# S03.net
KiCad netlist of a schematic drawn in Altium Designer
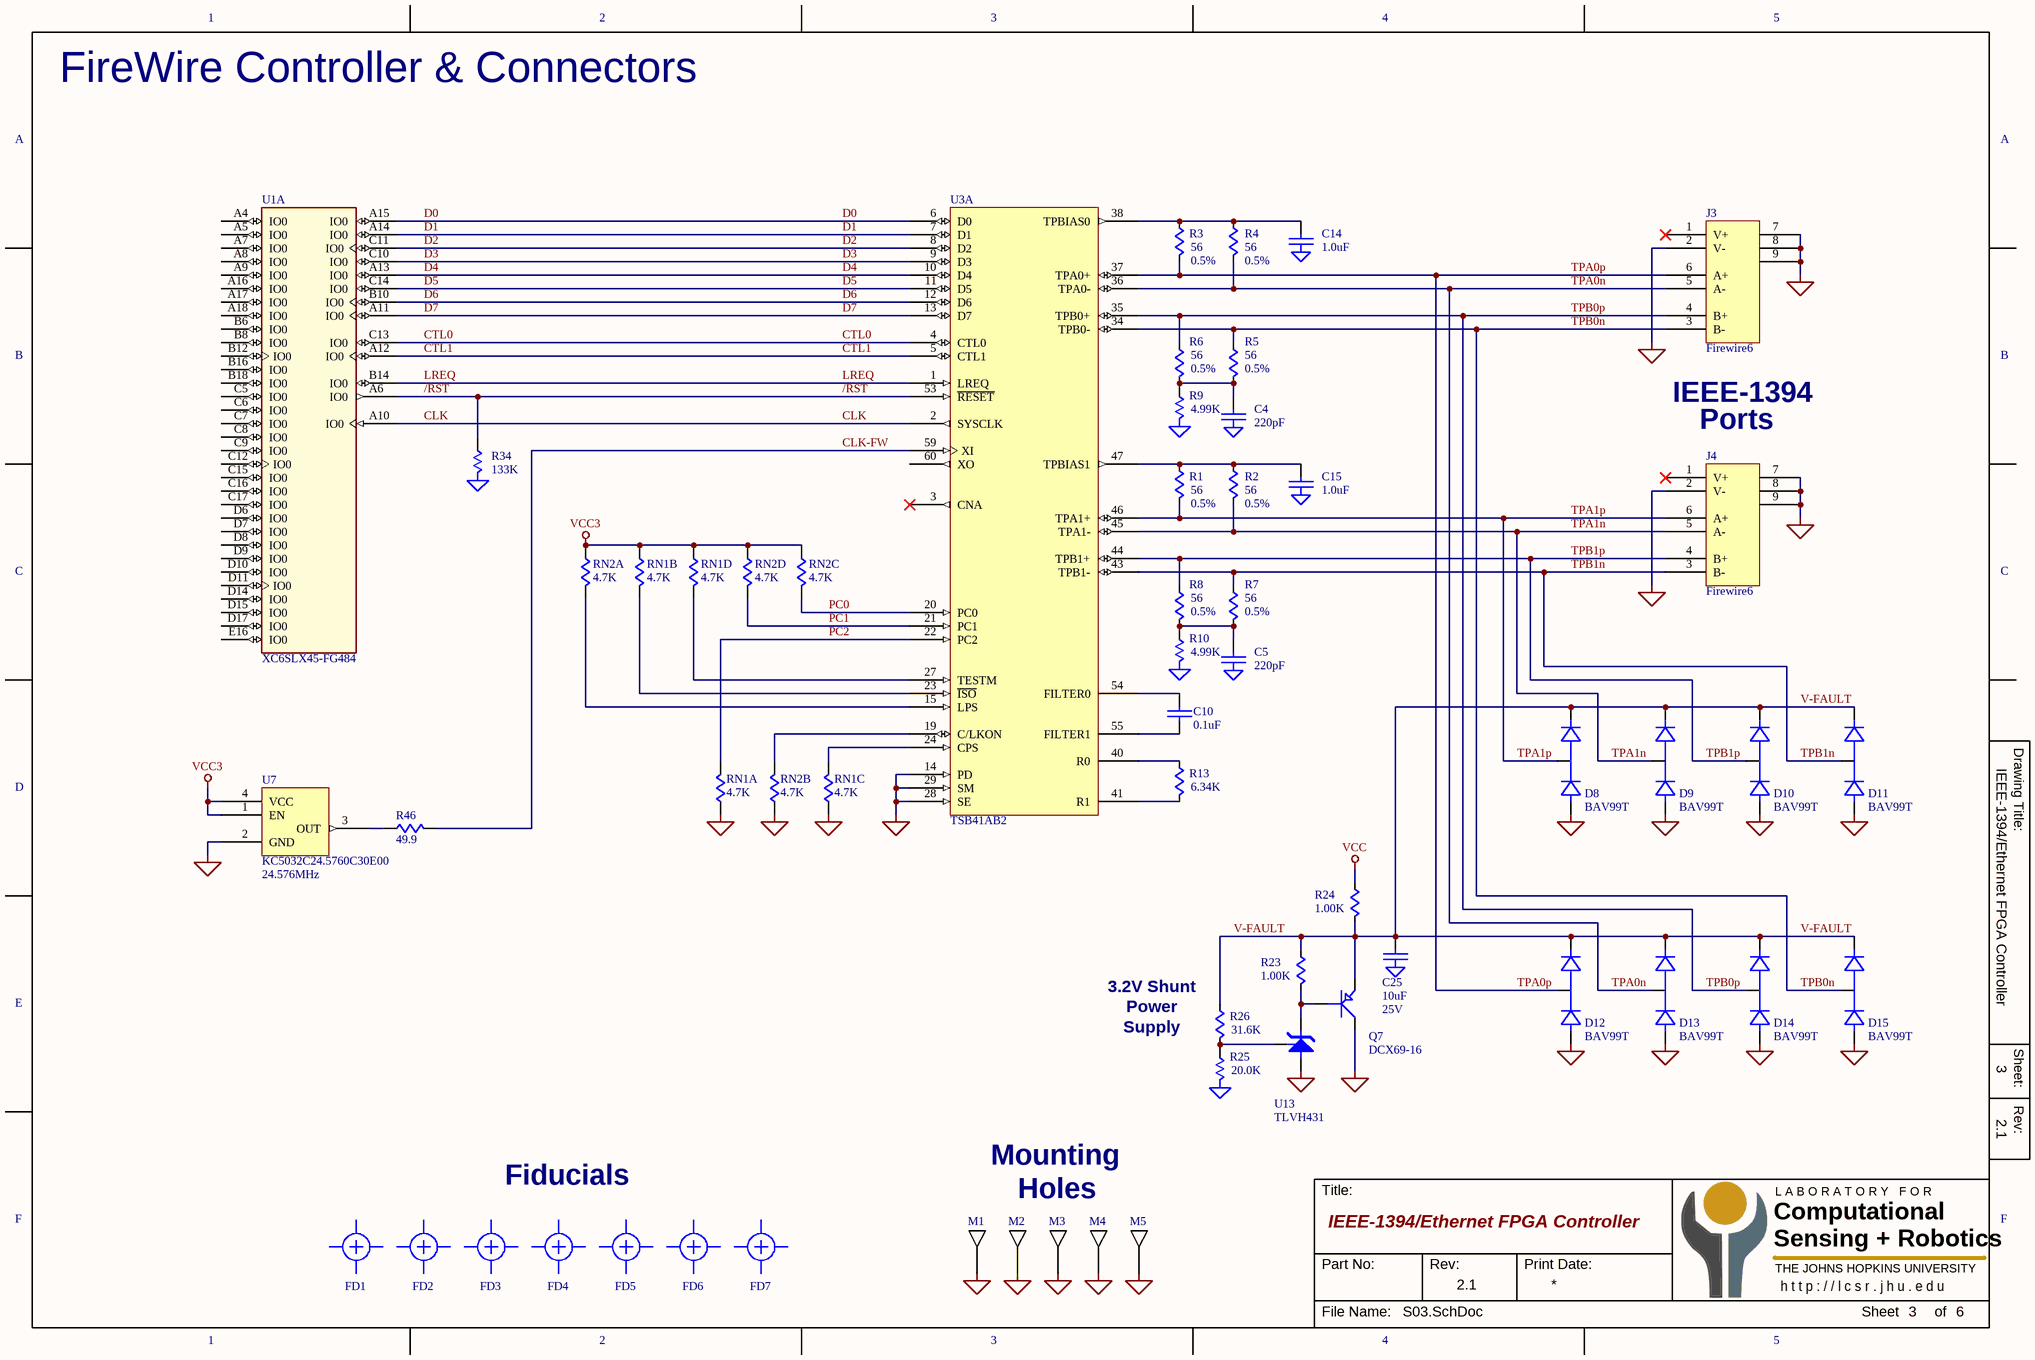
[diagram p0: S03.SchDoc]

(export (version "E")
  (design (tool "Eeschema 10.0.6"))
  (components
    (comp (ref "C4") (value "220pF") (footprint "C0603") (libsource (lib "LibJHU") (part "CAP-GND")))
    (comp (ref "C5") (value "220pF") (footprint "C0603") (libsource (lib "LibJHU") (part "CAP-GND")))
    (comp (ref "C10") (value "0.1uF") (footprint "C0603") (libsource (lib "LibJHU") (part "CAP")))
    (comp (ref "C14") (value "1.0uF") (footprint "C0603") (libsource (lib "LibJHU") (part "CAP-GND")))
    (comp (ref "C15") (value "1.0uF") (footprint "C0603") (libsource (lib "LibJHU") (part "CAP-GND")))
    (comp (ref "C25")
      (value "10uF")
      (footprint "C0805")
      (fields (field (name "ALTIUM_UNNAMED_1") "25V"))
      (libsource (lib "LibJHU") (part "CAP-GND"))
    )
    (comp (ref "D8") (value "BAV99T") (footprint "SOT-523") (libsource (lib "LibJHU") (part "DIODE-2/SER")))
    (comp (ref "D9") (value "BAV99T") (footprint "SOT-523") (libsource (lib "LibJHU") (part "DIODE-2/SER")))
    (comp (ref "D10") (value "BAV99T") (footprint "SOT-523") (libsource (lib "LibJHU") (part "DIODE-2/SER")))
    (comp (ref "D11") (value "BAV99T") (footprint "SOT-523") (libsource (lib "LibJHU") (part "DIODE-2/SER")))
    (comp (ref "D12") (value "BAV99T") (footprint "SOT-523") (libsource (lib "LibJHU") (part "DIODE-2/SER")))
    (comp (ref "D13") (value "BAV99T") (footprint "SOT-523") (libsource (lib "LibJHU") (part "DIODE-2/SER")))
    (comp (ref "D14") (value "BAV99T") (footprint "SOT-523") (libsource (lib "LibJHU") (part "DIODE-2/SER")))
    (comp (ref "D15") (value "BAV99T") (footprint "SOT-523") (libsource (lib "LibJHU") (part "DIODE-2/SER")))
    (comp (ref "FD1") (value "FD") (footprint "FD") (libsource (lib "LibJHU") (part "FD")))
    (comp (ref "FD2") (value "FD") (footprint "FD") (libsource (lib "LibJHU") (part "FD")))
    (comp (ref "FD3") (value "FD") (footprint "FD") (libsource (lib "LibJHU") (part "FD")))
    (comp (ref "FD4") (value "FD") (footprint "FD") (libsource (lib "LibJHU") (part "FD")))
    (comp (ref "FD5") (value "FD") (footprint "FD") (libsource (lib "LibJHU") (part "FD")))
    (comp (ref "FD6") (value "FD") (footprint "FD") (libsource (lib "LibJHU") (part "FD")))
    (comp (ref "FD7") (value "FD") (footprint "FD") (libsource (lib "LibJHU") (part "FD")))
    (comp (ref "J3")
      (value "Firewire6")
      (footprint "Firewire6-RA")
      (libsource (lib "LibJHU") (part "Firewire6"))
    )
    (comp (ref "J4")
      (value "Firewire6")
      (footprint "Firewire6-RA")
      (libsource (lib "LibJHU") (part "Firewire6"))
    )
    (comp (ref "M1")
      (value "MHOLE")
      (footprint "MHOLE4")
      (description "Mounting Hole")
      (libsource (lib "LibJHU") (part "MHOLE"))
    )
    (comp (ref "M2")
      (value "MHOLE")
      (footprint "MHOLE4")
      (description "Mounting Hole")
      (libsource (lib "LibJHU") (part "MHOLE"))
    )
    (comp (ref "M3")
      (value "MHOLE")
      (footprint "MHOLE4")
      (description "Mounting Hole")
      (libsource (lib "LibJHU") (part "MHOLE"))
    )
    (comp (ref "M4")
      (value "MHOLE")
      (footprint "MHOLE4")
      (description "Mounting Hole")
      (libsource (lib "LibJHU") (part "MHOLE"))
    )
    (comp (ref "M5")
      (value "MHOLE")
      (footprint "MHOLE4")
      (description "Mounting Hole")
      (libsource (lib "LibJHU") (part "MHOLE"))
    )
    (comp (ref "Q7") (value "DCX69-16") (footprint "SOT-89") (libsource (lib "LibJHU") (part "PNP-SM")))
    (comp (ref "R1")
      (value "56")
      (footprint "R0603")
      (fields (field (name "TOLL") "0.5%"))
      (libsource (lib "LibJHU") (part "R-MINI"))
    )
    (comp (ref "R2")
      (value "56")
      (footprint "R0603")
      (fields (field (name "TOLL") "0.5%"))
      (libsource (lib "LibJHU") (part "R-MINI"))
    )
    (comp (ref "R3")
      (value "56")
      (footprint "R0603")
      (fields (field (name "TOLL") "0.5%"))
      (libsource (lib "LibJHU") (part "R-MINI"))
    )
    (comp (ref "R4")
      (value "56")
      (footprint "R0603")
      (fields (field (name "TOLL") "0.5%"))
      (libsource (lib "LibJHU") (part "R-MINI"))
    )
    (comp (ref "R5")
      (value "56")
      (footprint "R0603")
      (fields (field (name "TOLL") "0.5%"))
      (libsource (lib "LibJHU") (part "R-MINI"))
    )
    (comp (ref "R6")
      (value "56")
      (footprint "R0603")
      (fields (field (name "TOLL") "0.5%"))
      (libsource (lib "LibJHU") (part "R-MINI"))
    )
    (comp (ref "R7")
      (value "56")
      (footprint "R0603")
      (fields (field (name "TOLL") "0.5%"))
      (libsource (lib "LibJHU") (part "R-MINI"))
    )
    (comp (ref "R8")
      (value "56")
      (footprint "R0603")
      (fields (field (name "TOLL") "0.5%"))
      (libsource (lib "LibJHU") (part "R-MINI"))
    )
    (comp (ref "R9") (value "4.99K") (footprint "R0603") (libsource (lib "") (part "R-GND_1")))
    (comp (ref "R10") (value "4.99K") (footprint "R0603") (libsource (lib "") (part "R-GND_1")))
    (comp (ref "R13") (value "6.34K") (footprint "R0603") (libsource (lib "LibJHU") (part "R-MINI")))
    (comp (ref "R23") (value "1.00K") (footprint "R0603") (libsource (lib "LibJHU") (part "R-MINI")))
    (comp (ref "R24") (value "1.00K") (footprint "R0603") (libsource (lib "LibJHU") (part "R-MINI")))
    (comp (ref "R25") (value "20.0K") (footprint "R0603") (libsource (lib "") (part "R-GND_1")))
    (comp (ref "R26") (value "31.6K") (footprint "R0603") (libsource (lib "LibJHU") (part "R-MINI")))
    (comp (ref "R34") (value "133K") (footprint "R0603") (libsource (lib "LibJHU") (part "R-GND")))
    (comp (ref "R46") (value "49.9") (footprint "R0402") (libsource (lib "LibJHU") (part "R")))
    (comp (ref "RN1")
      (value "4.7K")
      (footprint "RN-742C083")
      (libsource (lib "LibJHU") (part "RN-DISC-SM-4X"))
    )
    (comp (ref "RN2")
      (value "4.7K")
      (footprint "RN-742C083")
      (libsource (lib "LibJHU") (part "RN-DISC-SM-4X"))
    )
    (comp (ref "U1")
      (value "XC6SLX45-FG484")
      (footprint "FG-484")
      (libsource (lib "LibJHU") (part "XC6SLX45-FG484"))
    )
    (comp (ref "U3")
      (value "TSB41AB2")
      (footprint "PQFP-65")
      (description "IEEE 1394a-2000 Two-port Transceiver/Arbiter")
      (libsource (lib "LibJHU") (part "TSB41AB2"))
    )
    (comp (ref "U7")
      (value "KC5032C24.5760C30E00")
      (footprint "OSC-3x5MM")
      (fields (field (name "FREQ") "24.576MHz"))
      (libsource (lib "LibJHU") (part "OSCILATOR"))
    )
    (comp (ref "U13") (value "TLVH431") (footprint "SC70-6") (libsource (lib "LibJHU") (part "TLVH431-SC70")))
  )
  (nets
    (net (code "1") (name "/CLK") (class "Default")
      (node (ref "U1") (pin "A10") (pinfunction "IO0_A10") (pintype "input"))
      (node (ref "U3") (pin "2") (pinfunction "SYSCLK_2") (pintype "output"))
    )
    (net (code "2") (name "/CLK-FW") (class "Default")
      (node (ref "R46") (pin "2") (pinfunction "2_2") (pintype "passive"))
      (node (ref "U3") (pin "59") (pinfunction "XI_59") (pintype "input"))
    )
    (net (code "3") (name "/CTL0") (class "Default")
      (node (ref "U1") (pin "C13") (pinfunction "IO0_C13") (pintype "bidirectional"))
      (node (ref "U3") (pin "4") (pinfunction "CTL0_4") (pintype "bidirectional"))
    )
    (net (code "4") (name "/CTL1") (class "Default")
      (node (ref "U1") (pin "A12") (pinfunction "IO0_A12") (pintype "bidirectional"))
      (node (ref "U3") (pin "5") (pinfunction "CTL1_5") (pintype "bidirectional"))
    )
    (net (code "5") (name "/D0") (class "Default")
      (node (ref "U1") (pin "A15") (pinfunction "IO0_A15") (pintype "bidirectional"))
      (node (ref "U3") (pin "6") (pinfunction "D0_6") (pintype "bidirectional"))
    )
    (net (code "6") (name "/D1") (class "Default")
      (node (ref "U1") (pin "A14") (pinfunction "IO0_A14") (pintype "bidirectional"))
      (node (ref "U3") (pin "7") (pinfunction "D1_7") (pintype "bidirectional"))
    )
    (net (code "7") (name "/D2") (class "Default")
      (node (ref "U1") (pin "C11") (pinfunction "IO0_C11") (pintype "bidirectional"))
      (node (ref "U3") (pin "8") (pinfunction "D2_8") (pintype "bidirectional"))
    )
    (net (code "8") (name "/D3") (class "Default")
      (node (ref "U1") (pin "C10") (pinfunction "IO0_C10") (pintype "bidirectional"))
      (node (ref "U3") (pin "9") (pinfunction "D3_9") (pintype "bidirectional"))
    )
    (net (code "9") (name "/D4") (class "Default")
      (node (ref "U1") (pin "A13") (pinfunction "IO0_A13") (pintype "bidirectional"))
      (node (ref "U3") (pin "10") (pinfunction "D4_10") (pintype "bidirectional"))
    )
    (net (code "10") (name "/D5") (class "Default")
      (node (ref "U1") (pin "C14") (pinfunction "IO0_C14") (pintype "bidirectional"))
      (node (ref "U3") (pin "11") (pinfunction "D5_11") (pintype "bidirectional"))
    )
    (net (code "11") (name "/D6") (class "Default")
      (node (ref "U1") (pin "B10") (pinfunction "IO0_B10") (pintype "bidirectional"))
      (node (ref "U3") (pin "12") (pinfunction "D6_12") (pintype "bidirectional"))
    )
    (net (code "12") (name "/D7") (class "Default")
      (node (ref "U1") (pin "A11") (pinfunction "IO0_A11") (pintype "bidirectional"))
      (node (ref "U3") (pin "13") (pinfunction "D7_13") (pintype "bidirectional"))
    )
    (net (code "13") (name "/LREQ") (class "Default")
      (node (ref "U1") (pin "B14") (pinfunction "IO0_B14") (pintype "bidirectional"))
      (node (ref "U3") (pin "1") (pinfunction "LREQ_1") (pintype "input"))
    )
    (net (code "14") (name "/PC0") (class "Default")
      (node (ref "RN2") (pin "6") (pinfunction "6_6") (pintype "passive"))
      (node (ref "U3") (pin "20") (pinfunction "PC0_20") (pintype "input"))
    )
    (net (code "15") (name "/PC1") (class "Default")
      (node (ref "RN2") (pin "5") (pinfunction "5_5") (pintype "passive"))
      (node (ref "U3") (pin "21") (pinfunction "PC1_21") (pintype "input"))
    )
    (net (code "16") (name "/PC2") (class "Default")
      (node (ref "RN1") (pin "8") (pinfunction "8_8") (pintype "passive"))
      (node (ref "U3") (pin "22") (pinfunction "PC2_22") (pintype "input"))
    )
    (net (code "17") (name "/TPA0n") (class "Default")
      (node (ref "D13") (pin "3") (pinfunction "COM_3") (pintype "passive"))
      (node (ref "J3") (pin "5") (pinfunction "A-_5") (pintype "passive"))
      (node (ref "R4") (pin "2") (pinfunction "2_2") (pintype "passive"))
      (node (ref "U3") (pin "36") (pinfunction "TPA0-_36") (pintype "bidirectional"))
    )
    (net (code "18") (name "/TPA0p") (class "Default")
      (node (ref "D12") (pin "3") (pinfunction "COM_3") (pintype "passive"))
      (node (ref "J3") (pin "6") (pinfunction "A+_6") (pintype "passive"))
      (node (ref "R3") (pin "2") (pinfunction "2_2") (pintype "passive"))
      (node (ref "U3") (pin "37") (pinfunction "TPA0+_37") (pintype "bidirectional"))
    )
    (net (code "19") (name "/TPA1n") (class "Default")
      (node (ref "D9") (pin "3") (pinfunction "COM_3") (pintype "passive"))
      (node (ref "J4") (pin "5") (pinfunction "A-_5") (pintype "passive"))
      (node (ref "R2") (pin "2") (pinfunction "2_2") (pintype "passive"))
      (node (ref "U3") (pin "45") (pinfunction "TPA1-_45") (pintype "bidirectional"))
    )
    (net (code "20") (name "/TPA1p") (class "Default")
      (node (ref "D8") (pin "3") (pinfunction "COM_3") (pintype "passive"))
      (node (ref "J4") (pin "6") (pinfunction "A+_6") (pintype "passive"))
      (node (ref "R1") (pin "2") (pinfunction "2_2") (pintype "passive"))
      (node (ref "U3") (pin "46") (pinfunction "TPA1+_46") (pintype "bidirectional"))
    )
    (net (code "21") (name "/TPB0n") (class "Default")
      (node (ref "D15") (pin "3") (pinfunction "COM_3") (pintype "passive"))
      (node (ref "J3") (pin "3") (pinfunction "B-_3") (pintype "passive"))
      (node (ref "R5") (pin "1") (pinfunction "1_1") (pintype "passive"))
      (node (ref "U3") (pin "34") (pinfunction "TPB0-_34") (pintype "bidirectional"))
    )
    (net (code "22") (name "/TPB0p") (class "Default")
      (node (ref "D14") (pin "3") (pinfunction "COM_3") (pintype "passive"))
      (node (ref "J3") (pin "4") (pinfunction "B+_4") (pintype "passive"))
      (node (ref "R6") (pin "1") (pinfunction "1_1") (pintype "passive"))
      (node (ref "U3") (pin "35") (pinfunction "TPB0+_35") (pintype "bidirectional"))
    )
    (net (code "23") (name "/TPB1n") (class "Default")
      (node (ref "D11") (pin "3") (pinfunction "COM_3") (pintype "passive"))
      (node (ref "J4") (pin "3") (pinfunction "B-_3") (pintype "passive"))
      (node (ref "R7") (pin "1") (pinfunction "1_1") (pintype "passive"))
      (node (ref "U3") (pin "43") (pinfunction "TPB1-_43") (pintype "bidirectional"))
    )
    (net (code "24") (name "/TPB1p") (class "Default")
      (node (ref "D10") (pin "3") (pinfunction "COM_3") (pintype "passive"))
      (node (ref "J4") (pin "4") (pinfunction "B+_4") (pintype "passive"))
      (node (ref "R8") (pin "1") (pinfunction "1_1") (pintype "passive"))
      (node (ref "U3") (pin "44") (pinfunction "TPB1+_44") (pintype "bidirectional"))
    )
    (net (code "25") (name "/V-FAULT") (class "Default")
      (node (ref "C25") (pin "1") (pintype "passive"))
      (node (ref "D10") (pin "2") (pinfunction "C_2") (pintype "passive"))
      (node (ref "D11") (pin "2") (pinfunction "C_2") (pintype "passive"))
      (node (ref "D12") (pin "2") (pinfunction "C_2") (pintype "passive"))
      (node (ref "D13") (pin "2") (pinfunction "C_2") (pintype "passive"))
      (node (ref "D14") (pin "2") (pinfunction "C_2") (pintype "passive"))
      (node (ref "D15") (pin "2") (pinfunction "C_2") (pintype "passive"))
      (node (ref "D8") (pin "2") (pinfunction "C_2") (pintype "passive"))
      (node (ref "D9") (pin "2") (pinfunction "C_2") (pintype "passive"))
      (node (ref "Q7") (pin "2") (pinfunction "E_2") (pintype "passive"))
      (node (ref "R23") (pin "1") (pinfunction "1_1") (pintype "passive"))
      (node (ref "R24") (pin "2") (pinfunction "2_2") (pintype "passive"))
      (node (ref "R26") (pin "1") (pinfunction "1_1") (pintype "passive"))
    )
    (net (code "26") (name "/{slash}RST") (class "Default")
      (node (ref "R34") (pin "1") (pinfunction "1_1") (pintype "passive"))
      (node (ref "U1") (pin "A6") (pinfunction "IO0_A6") (pintype "output"))
      (node (ref "U3") (pin "53") (pinfunction "~{RESET}_53") (pintype "input"))
    )
    (net (code "27") (name "GND") (class "Default")
      (node (ref "C14") (pin "2") (pinfunction "GND_2") (pintype "power_in"))
      (node (ref "C15") (pin "2") (pinfunction "GND_2") (pintype "power_in"))
      (node (ref "C25") (pin "2") (pinfunction "GND_2") (pintype "power_in"))
      (node (ref "C4") (pin "2") (pinfunction "GND_2") (pintype "power_in"))
      (node (ref "C5") (pin "2") (pinfunction "GND_2") (pintype "power_in"))
      (node (ref "D10") (pin "1") (pinfunction "A_1") (pintype "passive"))
      (node (ref "D11") (pin "1") (pinfunction "A_1") (pintype "passive"))
      (node (ref "D12") (pin "1") (pinfunction "A_1") (pintype "passive"))
      (node (ref "D13") (pin "1") (pinfunction "A_1") (pintype "passive"))
      (node (ref "D14") (pin "1") (pinfunction "A_1") (pintype "passive"))
      (node (ref "D15") (pin "1") (pinfunction "A_1") (pintype "passive"))
      (node (ref "D8") (pin "1") (pinfunction "A_1") (pintype "passive"))
      (node (ref "D9") (pin "1") (pinfunction "A_1") (pintype "passive"))
      (node (ref "J3") (pin "2") (pinfunction "V-_2") (pintype "power_in"))
      (node (ref "J3") (pin "7") (pinfunction "CHASIS_7") (pintype "power_in"))
      (node (ref "J3") (pin "8") (pinfunction "CHASIS_8") (pintype "power_in"))
      (node (ref "J3") (pin "9") (pinfunction "CHASIS_9") (pintype "power_in"))
      (node (ref "J4") (pin "2") (pinfunction "V-_2") (pintype "power_in"))
      (node (ref "J4") (pin "7") (pinfunction "CHASIS_7") (pintype "power_in"))
      (node (ref "J4") (pin "8") (pinfunction "CHASIS_8") (pintype "power_in"))
      (node (ref "J4") (pin "9") (pinfunction "CHASIS_9") (pintype "power_in"))
      (node (ref "M1") (pin "1") (pinfunction "1_1") (pintype "passive"))
      (node (ref "M2") (pin "1") (pinfunction "1_1") (pintype "passive"))
      (node (ref "M3") (pin "1") (pinfunction "1_1") (pintype "passive"))
      (node (ref "M4") (pin "1") (pinfunction "1_1") (pintype "passive"))
      (node (ref "M5") (pin "1") (pinfunction "1_1") (pintype "passive"))
      (node (ref "Q7") (pin "3") (pinfunction "C_3") (pintype "passive"))
      (node (ref "R10") (pin "2") (pinfunction "GND_2") (pintype "power_in"))
      (node (ref "R25") (pin "2") (pinfunction "GND_2") (pintype "power_in"))
      (node (ref "R34") (pin "2") (pinfunction "GND_2") (pintype "power_in"))
      (node (ref "R9") (pin "2") (pinfunction "GND_2") (pintype "power_in"))
      (node (ref "RN1") (pin "1") (pinfunction "1_1") (pintype "passive"))
      (node (ref "RN1") (pin "3") (pinfunction "3_3") (pintype "passive"))
      (node (ref "RN2") (pin "2") (pinfunction "2_2") (pintype "passive"))
      (node (ref "U13") (pin "6") (pinfunction "A_6") (pintype "passive"))
      (node (ref "U3") (pin "14") (pinfunction "PD_14") (pintype "input"))
      (node (ref "U3") (pin "28") (pinfunction "SE_28") (pintype "input"))
      (node (ref "U3") (pin "29") (pinfunction "SM_29") (pintype "input"))
      (node (ref "U7") (pin "2") (pinfunction "GND_2") (pintype "power_in"))
    )
    (net (code "28") (name "Net-(C4-Pad1)") (class "Default")
      (node (ref "C4") (pin "1") (pintype "passive"))
      (node (ref "R5") (pin "2") (pinfunction "2_2") (pintype "passive"))
      (node (ref "R6") (pin "2") (pinfunction "2_2") (pintype "passive"))
      (node (ref "R9") (pin "1") (pinfunction "1_1") (pintype "passive"))
    )
    (net (code "29") (name "Net-(C5-Pad1)") (class "Default")
      (node (ref "C5") (pin "1") (pintype "passive"))
      (node (ref "R10") (pin "1") (pinfunction "1_1") (pintype "passive"))
      (node (ref "R7") (pin "2") (pinfunction "2_2") (pintype "passive"))
      (node (ref "R8") (pin "2") (pinfunction "2_2") (pintype "passive"))
    )
    (net (code "30") (name "Net-(Q7-B)") (class "Default")
      (node (ref "Q7") (pin "1") (pinfunction "B_1") (pintype "passive"))
      (node (ref "R23") (pin "2") (pinfunction "2_2") (pintype "passive"))
      (node (ref "U13") (pin "1") (pinfunction "C_1") (pintype "passive"))
    )
    (net (code "31") (name "Net-(U3A-CPS)") (class "Default")
      (node (ref "RN1") (pin "6") (pinfunction "6_6") (pintype "passive"))
      (node (ref "U3") (pin "24") (pinfunction "CPS_24") (pintype "input"))
    )
    (net (code "32") (name "Net-(U3A-C{slash}LKON)") (class "Default")
      (node (ref "RN2") (pin "7") (pinfunction "7_7") (pintype "passive"))
      (node (ref "U3") (pin "19") (pinfunction "C/LKON_19") (pintype "bidirectional"))
    )
    (net (code "33") (name "Net-(U3A-FILTER0)") (class "Default")
      (node (ref "C10") (pin "1") (pintype "passive"))
      (node (ref "U3") (pin "54") (pinfunction "FILTER0_54") (pintype "passive"))
    )
    (net (code "34") (name "Net-(U3A-FILTER1)") (class "Default")
      (node (ref "C10") (pin "2") (pintype "passive"))
      (node (ref "U3") (pin "55") (pinfunction "FILTER1_55") (pintype "passive"))
    )
    (net (code "35") (name "Net-(U3A-LPS)") (class "Default")
      (node (ref "RN2") (pin "8") (pinfunction "8_8") (pintype "passive"))
      (node (ref "U3") (pin "15") (pinfunction "LPS_15") (pintype "input"))
    )
    (net (code "36") (name "Net-(U3A-R0)") (class "Default")
      (node (ref "R13") (pin "1") (pinfunction "1_1") (pintype "passive"))
      (node (ref "U3") (pin "40") (pinfunction "R0_40") (pintype "passive"))
    )
    (net (code "37") (name "Net-(U3A-R1)") (class "Default")
      (node (ref "R13") (pin "2") (pinfunction "2_2") (pintype "passive"))
      (node (ref "U3") (pin "41") (pinfunction "R1_41") (pintype "passive"))
    )
    (net (code "38") (name "Net-(U3A-TESTM)") (class "Default")
      (node (ref "RN1") (pin "5") (pinfunction "5_5") (pintype "passive"))
      (node (ref "U3") (pin "27") (pinfunction "TESTM_27") (pintype "input"))
    )
    (net (code "39") (name "Net-(U3A-TPBIAS0)") (class "Default")
      (node (ref "C14") (pin "1") (pintype "passive"))
      (node (ref "R3") (pin "1") (pinfunction "1_1") (pintype "passive"))
      (node (ref "R4") (pin "1") (pinfunction "1_1") (pintype "passive"))
      (node (ref "U3") (pin "38") (pinfunction "TPBIAS0_38") (pintype "output"))
    )
    (net (code "40") (name "Net-(U3A-TPBIAS1)") (class "Default")
      (node (ref "C15") (pin "1") (pintype "passive"))
      (node (ref "R1") (pin "1") (pinfunction "1_1") (pintype "passive"))
      (node (ref "R2") (pin "1") (pinfunction "1_1") (pintype "passive"))
      (node (ref "U3") (pin "47") (pinfunction "TPBIAS1_47") (pintype "output"))
    )
    (net (code "41") (name "Net-(U3A-~{ISO})") (class "Default")
      (node (ref "RN1") (pin "7") (pinfunction "7_7") (pintype "passive"))
      (node (ref "U3") (pin "23") (pinfunction "~{ISO}_23") (pintype "input"))
    )
    (net (code "42") (name "Net-(U7-OUT)") (class "Default")
      (node (ref "R46") (pin "1") (pinfunction "1_1") (pintype "passive"))
      (node (ref "U7") (pin "3") (pinfunction "OUT_3") (pintype "output"))
    )
    (net (code "43") (name "Net-(U13-ADJ)") (class "Default")
      (node (ref "R25") (pin "1") (pinfunction "1_1") (pintype "passive"))
      (node (ref "R26") (pin "2") (pinfunction "2_2") (pintype "passive"))
      (node (ref "U13") (pin "3") (pinfunction "ADJ_3") (pintype "tri_state"))
    )
    (net (code "44") (name "VCC") (class "Default")
      (node (ref "R24") (pin "1") (pinfunction "1_1") (pintype "passive"))
    )
    (net (code "45") (name "VCC3") (class "Default")
      (node (ref "RN1") (pin "2") (pinfunction "2_2") (pintype "passive"))
      (node (ref "RN1") (pin "4") (pinfunction "4_4") (pintype "passive"))
      (node (ref "RN2") (pin "1") (pinfunction "1_1") (pintype "passive"))
      (node (ref "RN2") (pin "3") (pinfunction "3_3") (pintype "passive"))
      (node (ref "RN2") (pin "4") (pinfunction "4_4") (pintype "passive"))
      (node (ref "U7") (pin "1") (pinfunction "EN_1") (pintype "passive"))
      (node (ref "U7") (pin "4") (pinfunction "VCC_4") (pintype "power_in"))
    )
    (net (code "46") (name "unconnected-(J3-V+-Pad1)") (class "Default")
      (node (ref "J3") (pin "1") (pinfunction "V+_1") (pintype "passive+no_connect"))
    )
    (net (code "47") (name "unconnected-(J4-V+-Pad1)") (class "Default")
      (node (ref "J4") (pin "1") (pinfunction "V+_1") (pintype "passive+no_connect"))
    )
    (net (code "48") (name "unconnected-(U1A-IO0-PadA4)") (class "Default")
      (node (ref "U1") (pin "A4") (pinfunction "IO0_A4") (pintype "bidirectional"))
    )
    (net (code "49") (name "unconnected-(U1A-IO0-PadA5)") (class "Default")
      (node (ref "U1") (pin "A5") (pinfunction "IO0_A5") (pintype "bidirectional"))
    )
    (net (code "50") (name "unconnected-(U1A-IO0-PadA7)") (class "Default")
      (node (ref "U1") (pin "A7") (pinfunction "IO0_A7") (pintype "bidirectional"))
    )
    (net (code "51") (name "unconnected-(U1A-IO0-PadA8)") (class "Default")
      (node (ref "U1") (pin "A8") (pinfunction "IO0_A8") (pintype "bidirectional"))
    )
    (net (code "52") (name "unconnected-(U1A-IO0-PadA9)") (class "Default")
      (node (ref "U1") (pin "A9") (pinfunction "IO0_A9") (pintype "bidirectional"))
    )
    (net (code "53") (name "unconnected-(U1A-IO0-PadA16)") (class "Default")
      (node (ref "U1") (pin "A16") (pinfunction "IO0_A16") (pintype "bidirectional"))
    )
    (net (code "54") (name "unconnected-(U1A-IO0-PadA17)") (class "Default")
      (node (ref "U1") (pin "A17") (pinfunction "IO0_A17") (pintype "bidirectional"))
    )
    (net (code "55") (name "unconnected-(U1A-IO0-PadA18)") (class "Default")
      (node (ref "U1") (pin "A18") (pinfunction "IO0_A18") (pintype "bidirectional"))
    )
    (net (code "56") (name "unconnected-(U1A-IO0-PadB6)") (class "Default")
      (node (ref "U1") (pin "B6") (pinfunction "IO0_B6") (pintype "bidirectional"))
    )
    (net (code "57") (name "unconnected-(U1A-IO0-PadB8)") (class "Default")
      (node (ref "U1") (pin "B8") (pinfunction "IO0_B8") (pintype "bidirectional"))
    )
    (net (code "58") (name "unconnected-(U1A-IO0-PadB12)") (class "Default")
      (node (ref "U1") (pin "B12") (pinfunction "IO0_B12") (pintype "bidirectional"))
    )
    (net (code "59") (name "unconnected-(U1A-IO0-PadB16)") (class "Default")
      (node (ref "U1") (pin "B16") (pinfunction "IO0_B16") (pintype "bidirectional"))
    )
    (net (code "60") (name "unconnected-(U1A-IO0-PadB18)") (class "Default")
      (node (ref "U1") (pin "B18") (pinfunction "IO0_B18") (pintype "bidirectional"))
    )
    (net (code "61") (name "unconnected-(U1A-IO0-PadC5)") (class "Default")
      (node (ref "U1") (pin "C5") (pinfunction "IO0_C5") (pintype "bidirectional"))
    )
    (net (code "62") (name "unconnected-(U1A-IO0-PadC6)") (class "Default")
      (node (ref "U1") (pin "C6") (pinfunction "IO0_C6") (pintype "bidirectional"))
    )
    (net (code "63") (name "unconnected-(U1A-IO0-PadC7)") (class "Default")
      (node (ref "U1") (pin "C7") (pinfunction "IO0_C7") (pintype "bidirectional"))
    )
    (net (code "64") (name "unconnected-(U1A-IO0-PadC8)") (class "Default")
      (node (ref "U1") (pin "C8") (pinfunction "IO0_C8") (pintype "bidirectional"))
    )
    (net (code "65") (name "unconnected-(U1A-IO0-PadC9)") (class "Default")
      (node (ref "U1") (pin "C9") (pinfunction "IO0_C9") (pintype "bidirectional"))
    )
    (net (code "66") (name "unconnected-(U1A-IO0-PadC12)") (class "Default")
      (node (ref "U1") (pin "C12") (pinfunction "IO0_C12") (pintype "bidirectional"))
    )
    (net (code "67") (name "unconnected-(U1A-IO0-PadC15)") (class "Default")
      (node (ref "U1") (pin "C15") (pinfunction "IO0_C15") (pintype "bidirectional"))
    )
    (net (code "68") (name "unconnected-(U1A-IO0-PadC16)") (class "Default")
      (node (ref "U1") (pin "C16") (pinfunction "IO0_C16") (pintype "bidirectional"))
    )
    (net (code "69") (name "unconnected-(U1A-IO0-PadC17)") (class "Default")
      (node (ref "U1") (pin "C17") (pinfunction "IO0_C17") (pintype "bidirectional"))
    )
    (net (code "70") (name "unconnected-(U1A-IO0-PadD6)") (class "Default")
      (node (ref "U1") (pin "D6") (pinfunction "IO0_D6") (pintype "bidirectional"))
    )
    (net (code "71") (name "unconnected-(U1A-IO0-PadD7)") (class "Default")
      (node (ref "U1") (pin "D7") (pinfunction "IO0_D7") (pintype "bidirectional"))
    )
    (net (code "72") (name "unconnected-(U1A-IO0-PadD8)") (class "Default")
      (node (ref "U1") (pin "D8") (pinfunction "IO0_D8") (pintype "bidirectional"))
    )
    (net (code "73") (name "unconnected-(U1A-IO0-PadD9)") (class "Default")
      (node (ref "U1") (pin "D9") (pinfunction "IO0_D9") (pintype "bidirectional"))
    )
    (net (code "74") (name "unconnected-(U1A-IO0-PadD10)") (class "Default")
      (node (ref "U1") (pin "D10") (pinfunction "IO0_D10") (pintype "bidirectional"))
    )
    (net (code "75") (name "unconnected-(U1A-IO0-PadD11)") (class "Default")
      (node (ref "U1") (pin "D11") (pinfunction "IO0_D11") (pintype "bidirectional"))
    )
    (net (code "76") (name "unconnected-(U1A-IO0-PadD14)") (class "Default")
      (node (ref "U1") (pin "D14") (pinfunction "IO0_D14") (pintype "bidirectional"))
    )
    (net (code "77") (name "unconnected-(U1A-IO0-PadD15)") (class "Default")
      (node (ref "U1") (pin "D15") (pinfunction "IO0_D15") (pintype "bidirectional"))
    )
    (net (code "78") (name "unconnected-(U1A-IO0-PadD17)") (class "Default")
      (node (ref "U1") (pin "D17") (pinfunction "IO0_D17") (pintype "bidirectional"))
    )
    (net (code "79") (name "unconnected-(U1A-IO0-PadE16)") (class "Default")
      (node (ref "U1") (pin "E16") (pinfunction "IO0_E16") (pintype "bidirectional"))
    )
    (net (code "80") (name "unconnected-(U3A-CNA-Pad3)") (class "Default")
      (node (ref "U3") (pin "3") (pinfunction "CNA_3") (pintype "output+no_connect"))
    )
    (net (code "81") (name "unconnected-(U3A-XO-Pad60)") (class "Default")
      (node (ref "U3") (pin "60") (pinfunction "XO_60") (pintype "output"))
    )
  )
)
